# vfd_dcbus.net
KiCad netlist of a schematic drawn in EAGLE
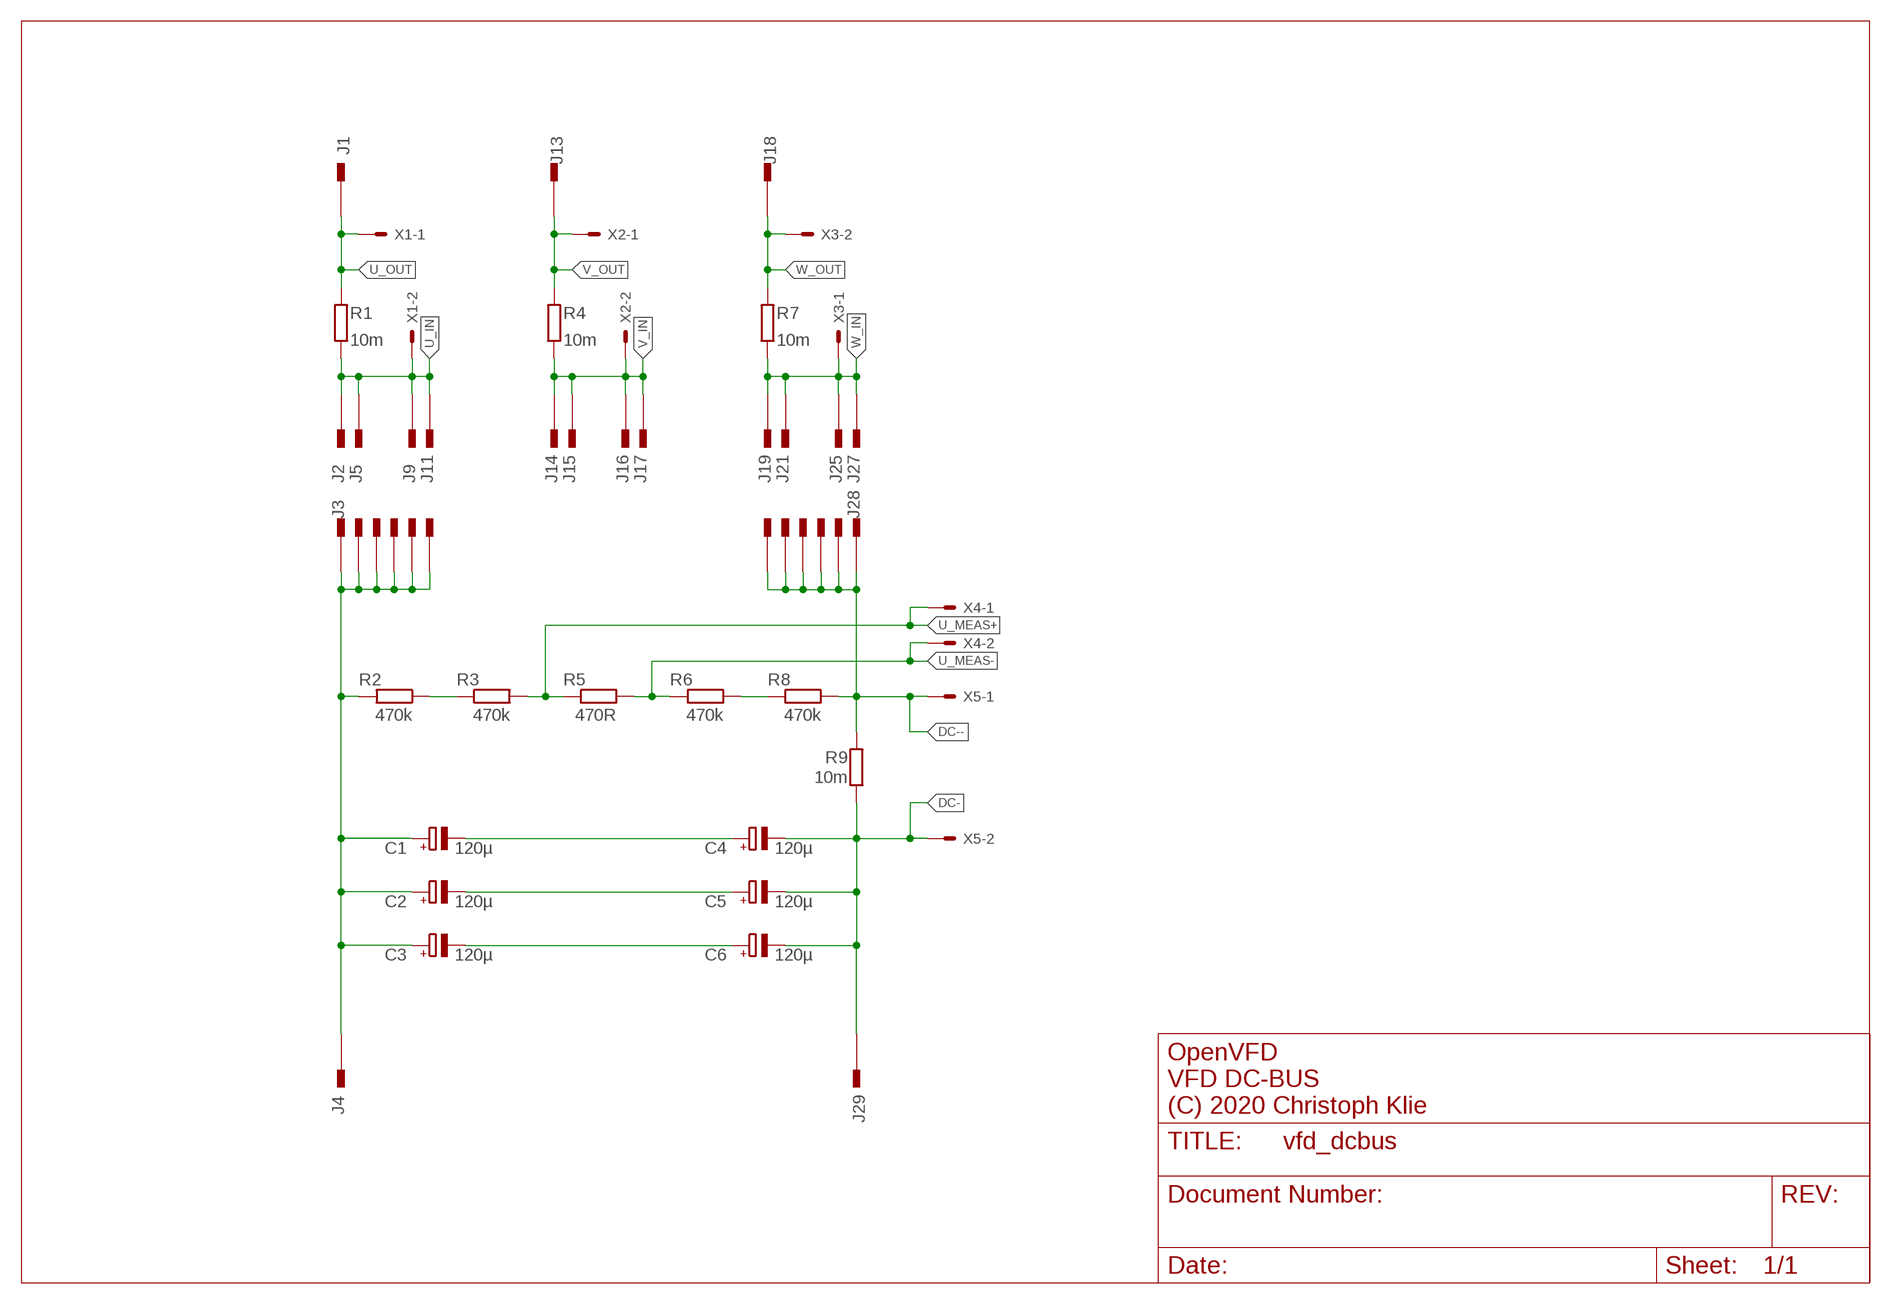
[diagram p0: schematic, sheet 1]

(export (version "E")
  (design (tool "Eeschema 10.0.6"))
  (components
    (comp (ref "C1")
      (value "120µ")
      (footprint "eagle-import:EB25D")
      (libsource (lib "eagle-import") (part "CPOL-EUE10-25"))
    )
    (comp (ref "C2")
      (value "120µ")
      (footprint "eagle-import:EB25D")
      (libsource (lib "eagle-import") (part "CPOL-EUE10-25"))
    )
    (comp (ref "C3")
      (value "120µ")
      (footprint "eagle-import:EB25D")
      (libsource (lib "eagle-import") (part "CPOL-EUE10-25"))
    )
    (comp (ref "C4")
      (value "120µ")
      (footprint "eagle-import:EB25D")
      (libsource (lib "eagle-import") (part "CPOL-EUE10-25"))
    )
    (comp (ref "C5")
      (value "120µ")
      (footprint "eagle-import:EB25D")
      (libsource (lib "eagle-import") (part "CPOL-EUE10-25"))
    )
    (comp (ref "C6")
      (value "120µ")
      (footprint "eagle-import:EB25D")
      (libsource (lib "eagle-import") (part "CPOL-EUE10-25"))
    )
    (comp (ref "J1")
      (value "PIN2F061.200")
      (footprint "eagle-import:F061.200")
      (libsource (lib "eagle-import") (part "PIN2F061.200"))
    )
    (comp (ref "J2")
      (value "PIN2F061.080")
      (footprint "eagle-import:F061.080")
      (libsource (lib "eagle-import") (part "PIN2F061.080"))
    )
    (comp (ref "J3")
      (value "PIN2F061.080")
      (footprint "eagle-import:F061.080")
      (libsource (lib "eagle-import") (part "PIN2F061.080"))
    )
    (comp (ref "J4")
      (value "PIN2F061.200")
      (footprint "eagle-import:F061.200")
      (libsource (lib "eagle-import") (part "PIN2F061.200"))
    )
    (comp (ref "J5")
      (value "PIN2F061.080")
      (footprint "eagle-import:F061.080")
      (libsource (lib "eagle-import") (part "PIN2F061.080"))
    )
    (comp (ref "J6")
      (value "PIN2F061.080")
      (footprint "eagle-import:F061.080")
      (libsource (lib "eagle-import") (part "PIN2F061.080"))
    )
    (comp (ref "J7")
      (value "PIN2F061.080")
      (footprint "eagle-import:F061.080")
      (libsource (lib "eagle-import") (part "PIN2F061.080"))
    )
    (comp (ref "J8")
      (value "PIN2F061.080")
      (footprint "eagle-import:F061.080")
      (libsource (lib "eagle-import") (part "PIN2F061.080"))
    )
    (comp (ref "J9")
      (value "PIN2F061.080")
      (footprint "eagle-import:F061.080")
      (libsource (lib "eagle-import") (part "PIN2F061.080"))
    )
    (comp (ref "J10")
      (value "PIN2F061.080")
      (footprint "eagle-import:F061.080")
      (libsource (lib "eagle-import") (part "PIN2F061.080"))
    )
    (comp (ref "J11")
      (value "PIN2F061.080")
      (footprint "eagle-import:F061.080")
      (libsource (lib "eagle-import") (part "PIN2F061.080"))
    )
    (comp (ref "J12")
      (value "PIN2F061.080")
      (footprint "eagle-import:F061.080")
      (libsource (lib "eagle-import") (part "PIN2F061.080"))
    )
    (comp (ref "J13")
      (value "PIN2F061.200")
      (footprint "eagle-import:F061.200")
      (libsource (lib "eagle-import") (part "PIN2F061.200"))
    )
    (comp (ref "J14")
      (value "PIN2F061.080")
      (footprint "eagle-import:F061.080")
      (libsource (lib "eagle-import") (part "PIN2F061.080"))
    )
    (comp (ref "J15")
      (value "PIN2F061.080")
      (footprint "eagle-import:F061.080")
      (libsource (lib "eagle-import") (part "PIN2F061.080"))
    )
    (comp (ref "J16")
      (value "PIN2F061.080")
      (footprint "eagle-import:F061.080")
      (libsource (lib "eagle-import") (part "PIN2F061.080"))
    )
    (comp (ref "J17")
      (value "PIN2F061.080")
      (footprint "eagle-import:F061.080")
      (libsource (lib "eagle-import") (part "PIN2F061.080"))
    )
    (comp (ref "J18")
      (value "PIN2F061.200")
      (footprint "eagle-import:F061.200")
      (libsource (lib "eagle-import") (part "PIN2F061.200"))
    )
    (comp (ref "J19")
      (value "PIN2F061.080")
      (footprint "eagle-import:F061.080")
      (libsource (lib "eagle-import") (part "PIN2F061.080"))
    )
    (comp (ref "J20")
      (value "PIN2F061.080")
      (footprint "eagle-import:F061.080")
      (libsource (lib "eagle-import") (part "PIN2F061.080"))
    )
    (comp (ref "J21")
      (value "PIN2F061.080")
      (footprint "eagle-import:F061.080")
      (libsource (lib "eagle-import") (part "PIN2F061.080"))
    )
    (comp (ref "J22")
      (value "PIN2F061.080")
      (footprint "eagle-import:F061.080")
      (libsource (lib "eagle-import") (part "PIN2F061.080"))
    )
    (comp (ref "J23")
      (value "PIN2F061.080")
      (footprint "eagle-import:F061.080")
      (libsource (lib "eagle-import") (part "PIN2F061.080"))
    )
    (comp (ref "J24")
      (value "PIN2F061.080")
      (footprint "eagle-import:F061.080")
      (libsource (lib "eagle-import") (part "PIN2F061.080"))
    )
    (comp (ref "J25")
      (value "PIN2F061.080")
      (footprint "eagle-import:F061.080")
      (libsource (lib "eagle-import") (part "PIN2F061.080"))
    )
    (comp (ref "J26")
      (value "PIN2F061.080")
      (footprint "eagle-import:F061.080")
      (libsource (lib "eagle-import") (part "PIN2F061.080"))
    )
    (comp (ref "J27")
      (value "PIN2F061.080")
      (footprint "eagle-import:F061.080")
      (libsource (lib "eagle-import") (part "PIN2F061.080"))
    )
    (comp (ref "J28")
      (value "PIN2F061.080")
      (footprint "eagle-import:F061.080")
      (libsource (lib "eagle-import") (part "PIN2F061.080"))
    )
    (comp (ref "J29")
      (value "PIN2F061.200")
      (footprint "eagle-import:F061.200")
      (libsource (lib "eagle-import") (part "PIN2F061.200"))
    )
    (comp (ref "R1")
      (value "10m")
      (footprint "eagle-import:R2512")
      (libsource (lib "eagle-import") (part "resistor_348_R-EU_R2512"))
    )
    (comp (ref "R2")
      (value "470k")
      (footprint "eagle-import:0207_5V")
      (libsource (lib "eagle-import") (part "R-EU_0207/5V"))
    )
    (comp (ref "R3")
      (value "470k")
      (footprint "eagle-import:0207_5V")
      (libsource (lib "eagle-import") (part "R-EU_0207/5V"))
    )
    (comp (ref "R4")
      (value "10m")
      (footprint "eagle-import:R2512")
      (libsource (lib "eagle-import") (part "resistor_348_R-EU_R2512"))
    )
    (comp (ref "R5")
      (value "470R")
      (footprint "eagle-import:R1206")
      (libsource (lib "eagle-import") (part "R-EU_R1206"))
    )
    (comp (ref "R6")
      (value "470k")
      (footprint "eagle-import:0207_5V")
      (libsource (lib "eagle-import") (part "R-EU_0207/5V"))
    )
    (comp (ref "R7")
      (value "10m")
      (footprint "eagle-import:R2512")
      (libsource (lib "eagle-import") (part "resistor_348_R-EU_R2512"))
    )
    (comp (ref "R8")
      (value "470k")
      (footprint "eagle-import:0207_5V")
      (libsource (lib "eagle-import") (part "R-EU_0207/5V"))
    )
    (comp (ref "R9")
      (value "10m")
      (footprint "eagle-import:R2512")
      (libsource (lib "eagle-import") (part "resistor_348_R-EU_R2512"))
    )
    (comp (ref "X1")
      (value "JST-XH-02-PIN-LONG-PAD")
      (footprint "eagle-import:JST-XH-02-PACKAGE-LONG-PAD")
      (fields (field (name "R") "JST XH2P ST"))
      (libsource (lib "eagle-import") (part "JST-XH-02-PIN-LONG-PAD"))
    )
    (comp (ref "X2")
      (value "JST-XH-02-PIN-LONG-PAD")
      (footprint "eagle-import:JST-XH-02-PACKAGE-LONG-PAD")
      (fields (field (name "R") "JST XH2P ST"))
      (libsource (lib "eagle-import") (part "JST-XH-02-PIN-LONG-PAD"))
    )
    (comp (ref "X3")
      (value "JST-XH-02-PIN-LONG-PAD")
      (footprint "eagle-import:JST-XH-02-PACKAGE-LONG-PAD")
      (fields (field (name "R") "JST XH2P ST"))
      (libsource (lib "eagle-import") (part "JST-XH-02-PIN-LONG-PAD"))
    )
    (comp (ref "X4")
      (value "JST-XH-02-PIN-LONG-PAD")
      (footprint "eagle-import:JST-XH-02-PACKAGE-LONG-PAD")
      (fields (field (name "R") "JST XH2P ST"))
      (libsource (lib "eagle-import") (part "JST-XH-02-PIN-LONG-PAD"))
    )
    (comp (ref "X5")
      (value "JST-XH-02-PIN-LONG-PAD")
      (footprint "eagle-import:JST-XH-02-PACKAGE-LONG-PAD")
      (fields (field (name "R") "JST XH2P ST"))
      (libsource (lib "eagle-import") (part "JST-XH-02-PIN-LONG-PAD"))
    )
  )
  (nets
    (net (code "1") (name "DC-") (class "Default")
      (node (ref "C4") (pin "-") (pinfunction "-_-") (pintype "passive"))
      (node (ref "C5") (pin "-") (pinfunction "-_-") (pintype "passive"))
      (node (ref "C6") (pin "-") (pinfunction "-_-") (pintype "passive"))
      (node (ref "J29") (pin "1A") (pinfunction "1_1A") (pintype "passive"))
      (node (ref "J29") (pin "1B") (pinfunction "1_1B") (pintype "passive"))
      (node (ref "R9") (pin "1") (pinfunction "1_1") (pintype "passive"))
      (node (ref "X5") (pin "2") (pinfunction "S_2") (pintype "passive"))
    )
    (net (code "2") (name "DC--") (class "Default")
      (node (ref "J20") (pin "1A") (pinfunction "1_1A") (pintype "passive"))
      (node (ref "J20") (pin "1B") (pinfunction "1_1B") (pintype "passive"))
      (node (ref "J22") (pin "1A") (pinfunction "1_1A") (pintype "passive"))
      (node (ref "J22") (pin "1B") (pinfunction "1_1B") (pintype "passive"))
      (node (ref "J23") (pin "1A") (pinfunction "1_1A") (pintype "passive"))
      (node (ref "J23") (pin "1B") (pinfunction "1_1B") (pintype "passive"))
      (node (ref "J24") (pin "1A") (pinfunction "1_1A") (pintype "passive"))
      (node (ref "J24") (pin "1B") (pinfunction "1_1B") (pintype "passive"))
      (node (ref "J26") (pin "1A") (pinfunction "1_1A") (pintype "passive"))
      (node (ref "J26") (pin "1B") (pinfunction "1_1B") (pintype "passive"))
      (node (ref "J28") (pin "1A") (pinfunction "1_1A") (pintype "passive"))
      (node (ref "J28") (pin "1B") (pinfunction "1_1B") (pintype "passive"))
      (node (ref "R8") (pin "2") (pinfunction "2_2") (pintype "passive"))
      (node (ref "R9") (pin "2") (pinfunction "2_2") (pintype "passive"))
      (node (ref "X5") (pin "1") (pinfunction "S_1") (pintype "passive"))
    )
    (net (code "3") (name "Net-(C1-Pad+)") (class "Default")
      (node (ref "C1") (pin "+") (pinfunction "+_+") (pintype "passive"))
      (node (ref "C2") (pin "+") (pinfunction "+_+") (pintype "passive"))
      (node (ref "C3") (pin "+") (pinfunction "+_+") (pintype "passive"))
      (node (ref "J10") (pin "1A") (pinfunction "1_1A") (pintype "passive"))
      (node (ref "J10") (pin "1B") (pinfunction "1_1B") (pintype "passive"))
      (node (ref "J12") (pin "1A") (pinfunction "1_1A") (pintype "passive"))
      (node (ref "J12") (pin "1B") (pinfunction "1_1B") (pintype "passive"))
      (node (ref "J3") (pin "1A") (pinfunction "1_1A") (pintype "passive"))
      (node (ref "J3") (pin "1B") (pinfunction "1_1B") (pintype "passive"))
      (node (ref "J4") (pin "1A") (pinfunction "1_1A") (pintype "passive"))
      (node (ref "J4") (pin "1B") (pinfunction "1_1B") (pintype "passive"))
      (node (ref "J6") (pin "1A") (pinfunction "1_1A") (pintype "passive"))
      (node (ref "J6") (pin "1B") (pinfunction "1_1B") (pintype "passive"))
      (node (ref "J7") (pin "1A") (pinfunction "1_1A") (pintype "passive"))
      (node (ref "J7") (pin "1B") (pinfunction "1_1B") (pintype "passive"))
      (node (ref "J8") (pin "1A") (pinfunction "1_1A") (pintype "passive"))
      (node (ref "J8") (pin "1B") (pinfunction "1_1B") (pintype "passive"))
      (node (ref "R2") (pin "2") (pinfunction "2_2") (pintype "passive"))
    )
    (net (code "4") (name "Net-(C1-Pad-)") (class "Default")
      (node (ref "C1") (pin "-") (pinfunction "-_-") (pintype "passive"))
      (node (ref "C4") (pin "+") (pinfunction "+_+") (pintype "passive"))
    )
    (net (code "5") (name "Net-(C2-Pad-)") (class "Default")
      (node (ref "C2") (pin "-") (pinfunction "-_-") (pintype "passive"))
      (node (ref "C5") (pin "+") (pinfunction "+_+") (pintype "passive"))
    )
    (net (code "6") (name "Net-(C3-Pad-)") (class "Default")
      (node (ref "C3") (pin "-") (pinfunction "-_-") (pintype "passive"))
      (node (ref "C6") (pin "+") (pinfunction "+_+") (pintype "passive"))
    )
    (net (code "7") (name "Net-(R2-Pad1)") (class "Default")
      (node (ref "R2") (pin "1") (pinfunction "1_1") (pintype "passive"))
      (node (ref "R3") (pin "1") (pinfunction "1_1") (pintype "passive"))
    )
    (net (code "8") (name "Net-(R6-Pad1)") (class "Default")
      (node (ref "R6") (pin "1") (pinfunction "1_1") (pintype "passive"))
      (node (ref "R8") (pin "1") (pinfunction "1_1") (pintype "passive"))
    )
    (net (code "9") (name "U_IN") (class "Default")
      (node (ref "J11") (pin "1A") (pinfunction "1_1A") (pintype "passive"))
      (node (ref "J11") (pin "1B") (pinfunction "1_1B") (pintype "passive"))
      (node (ref "J2") (pin "1A") (pinfunction "1_1A") (pintype "passive"))
      (node (ref "J2") (pin "1B") (pinfunction "1_1B") (pintype "passive"))
      (node (ref "J5") (pin "1A") (pinfunction "1_1A") (pintype "passive"))
      (node (ref "J5") (pin "1B") (pinfunction "1_1B") (pintype "passive"))
      (node (ref "J9") (pin "1A") (pinfunction "1_1A") (pintype "passive"))
      (node (ref "J9") (pin "1B") (pinfunction "1_1B") (pintype "passive"))
      (node (ref "R1") (pin "1") (pinfunction "1_1") (pintype "passive"))
      (node (ref "X1") (pin "2") (pinfunction "S_2") (pintype "passive"))
    )
    (net (code "10") (name "U_MEAS+") (class "Default")
      (node (ref "R3") (pin "2") (pinfunction "2_2") (pintype "passive"))
      (node (ref "R5") (pin "1") (pinfunction "1_1") (pintype "passive"))
      (node (ref "X4") (pin "1") (pinfunction "S_1") (pintype "passive"))
    )
    (net (code "11") (name "U_MEAS-") (class "Default")
      (node (ref "R5") (pin "2") (pinfunction "2_2") (pintype "passive"))
      (node (ref "R6") (pin "2") (pinfunction "2_2") (pintype "passive"))
      (node (ref "X4") (pin "2") (pinfunction "S_2") (pintype "passive"))
    )
    (net (code "12") (name "U_OUT") (class "Default")
      (node (ref "J1") (pin "1A") (pinfunction "1_1A") (pintype "passive"))
      (node (ref "J1") (pin "1B") (pinfunction "1_1B") (pintype "passive"))
      (node (ref "R1") (pin "2") (pinfunction "2_2") (pintype "passive"))
      (node (ref "X1") (pin "1") (pinfunction "S_1") (pintype "passive"))
    )
    (net (code "13") (name "V_IN") (class "Default")
      (node (ref "J14") (pin "1A") (pinfunction "1_1A") (pintype "passive"))
      (node (ref "J14") (pin "1B") (pinfunction "1_1B") (pintype "passive"))
      (node (ref "J15") (pin "1A") (pinfunction "1_1A") (pintype "passive"))
      (node (ref "J15") (pin "1B") (pinfunction "1_1B") (pintype "passive"))
      (node (ref "J16") (pin "1A") (pinfunction "1_1A") (pintype "passive"))
      (node (ref "J16") (pin "1B") (pinfunction "1_1B") (pintype "passive"))
      (node (ref "J17") (pin "1A") (pinfunction "1_1A") (pintype "passive"))
      (node (ref "J17") (pin "1B") (pinfunction "1_1B") (pintype "passive"))
      (node (ref "R4") (pin "1") (pinfunction "1_1") (pintype "passive"))
      (node (ref "X2") (pin "2") (pinfunction "S_2") (pintype "passive"))
    )
    (net (code "14") (name "V_OUT") (class "Default")
      (node (ref "J13") (pin "1A") (pinfunction "1_1A") (pintype "passive"))
      (node (ref "J13") (pin "1B") (pinfunction "1_1B") (pintype "passive"))
      (node (ref "R4") (pin "2") (pinfunction "2_2") (pintype "passive"))
      (node (ref "X2") (pin "1") (pinfunction "S_1") (pintype "passive"))
    )
    (net (code "15") (name "W_IN") (class "Default")
      (node (ref "J19") (pin "1A") (pinfunction "1_1A") (pintype "passive"))
      (node (ref "J19") (pin "1B") (pinfunction "1_1B") (pintype "passive"))
      (node (ref "J21") (pin "1A") (pinfunction "1_1A") (pintype "passive"))
      (node (ref "J21") (pin "1B") (pinfunction "1_1B") (pintype "passive"))
      (node (ref "J25") (pin "1A") (pinfunction "1_1A") (pintype "passive"))
      (node (ref "J25") (pin "1B") (pinfunction "1_1B") (pintype "passive"))
      (node (ref "J27") (pin "1A") (pinfunction "1_1A") (pintype "passive"))
      (node (ref "J27") (pin "1B") (pinfunction "1_1B") (pintype "passive"))
      (node (ref "R7") (pin "1") (pinfunction "1_1") (pintype "passive"))
      (node (ref "X3") (pin "1") (pinfunction "S_1") (pintype "passive"))
    )
    (net (code "16") (name "W_OUT") (class "Default")
      (node (ref "J18") (pin "1A") (pinfunction "1_1A") (pintype "passive"))
      (node (ref "J18") (pin "1B") (pinfunction "1_1B") (pintype "passive"))
      (node (ref "R7") (pin "2") (pinfunction "2_2") (pintype "passive"))
      (node (ref "X3") (pin "2") (pinfunction "S_2") (pintype "passive"))
    )
  )
)
